# PT_Connetions.net
KiCad netlist of a schematic drawn in Altium Designer
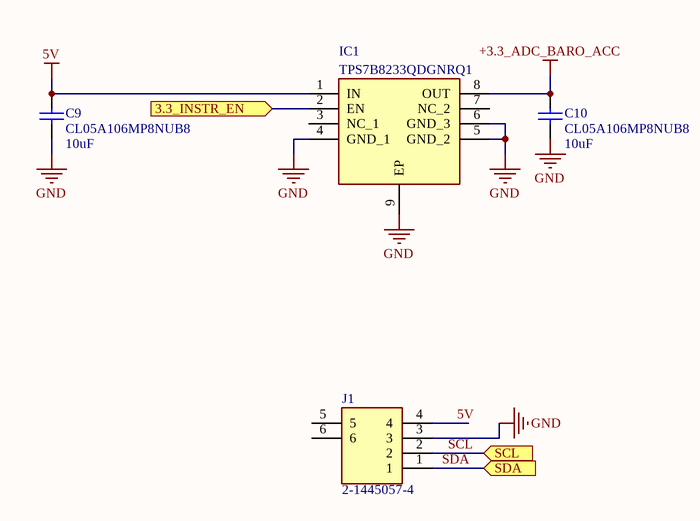
[diagram p0: PT_Connetions.SchDoc]

(export (version "E")
  (design (tool "Eeschema 10.0.6"))
  (components
    (comp (ref "C9")
      (value "CL05A106MP8NUB8")
      (footprint "0402")
      (description "Capacitor")
      (fields (field (name "ALTIUM_VALUE") "10uF") (field (name "PUBLISHER") "Altium Limited"))
      (libsource (lib "Miscellaneous Devices") (part "Cap"))
    )
    (comp (ref "C10")
      (value "CL05A106MP8NUB8")
      (footprint "0402")
      (description "Capacitor")
      (fields (field (name "ALTIUM_VALUE") "10uF") (field (name "PUBLISHER") "Altium Limited"))
      (libsource (lib "Miscellaneous Devices") (part "Cap"))
    )
    (comp (ref "IC1")
      (value "TPS7B8233QDGNRQ1")
      (footprint "SOP65P490X110-9N")
      (description "Integrated Circuit")
      (fields (field (name "MOUSER PART NUMBER") "595-TPS7B8233QDGNRQ1"))
      (libsource (lib "*") (part "TPS7B8233QDGNRQ1"))
    )
    (comp (ref "J1")
      (value "2-1445057-4")
      (footprint "214450574")
      (description "Connector")
      (fields (field (name "MOUSER PART NUMBER") "571-2-1445057-4"))
      (libsource (lib "*") (part "2-1445057-4"))
    )
  )
  (nets
    (net (code "1") (name "+3.3_ADC_BARO_ACC") (class "Default")
      (node (ref "C10") (pin "2") (pinfunction "2_2") (pintype "passive"))
      (node (ref "IC1") (pin "8") (pinfunction "OUT_8") (pintype "passive"))
    )
    (net (code "2") (name "/3.3_INSTR_EN") (class "Default")
      (node (ref "IC1") (pin "2") (pinfunction "EN_2") (pintype "passive"))
    )
    (net (code "3") (name "/SCL") (class "Default")
      (node (ref "J1") (pin "2") (pinfunction "2_2") (pintype "passive"))
    )
    (net (code "4") (name "/SDA") (class "Default")
      (node (ref "J1") (pin "1") (pinfunction "1_1") (pintype "passive"))
    )
    (net (code "5") (name "5V") (class "Default")
      (node (ref "C9") (pin "2") (pinfunction "2_2") (pintype "passive"))
      (node (ref "IC1") (pin "1") (pinfunction "IN_1") (pintype "passive"))
      (node (ref "J1") (pin "4") (pinfunction "4_4") (pintype "passive"))
    )
    (net (code "6") (name "GND") (class "Default")
      (node (ref "C10") (pin "1") (pinfunction "1_1") (pintype "passive"))
      (node (ref "C9") (pin "1") (pinfunction "1_1") (pintype "passive"))
      (node (ref "IC1") (pin "4") (pinfunction "GND_1_4") (pintype "passive"))
      (node (ref "IC1") (pin "5") (pinfunction "GND_2_5") (pintype "passive"))
      (node (ref "IC1") (pin "6") (pinfunction "GND_3_6") (pintype "passive"))
      (node (ref "IC1") (pin "9") (pinfunction "EP_9") (pintype "passive"))
      (node (ref "J1") (pin "3") (pinfunction "3_3") (pintype "passive"))
    )
    (net (code "7") (name "unconnected-(IC1-NC_1-Pad3)") (class "Default")
      (node (ref "IC1") (pin "3") (pinfunction "NC_1_3") (pintype "passive"))
    )
    (net (code "8") (name "unconnected-(IC1-NC_2-Pad7)") (class "Default")
      (node (ref "IC1") (pin "7") (pinfunction "NC_2_7") (pintype "passive"))
    )
    (net (code "9") (name "unconnected-(J1-Pad5)") (class "Default")
      (node (ref "J1") (pin "5") (pinfunction "5_5") (pintype "passive"))
    )
    (net (code "10") (name "unconnected-(J1-Pad6)") (class "Default")
      (node (ref "J1") (pin "6") (pinfunction "6_6") (pintype "passive"))
    )
  )
)
